# driverboard.net
KiCad netlist of a schematic drawn in Altium Designer
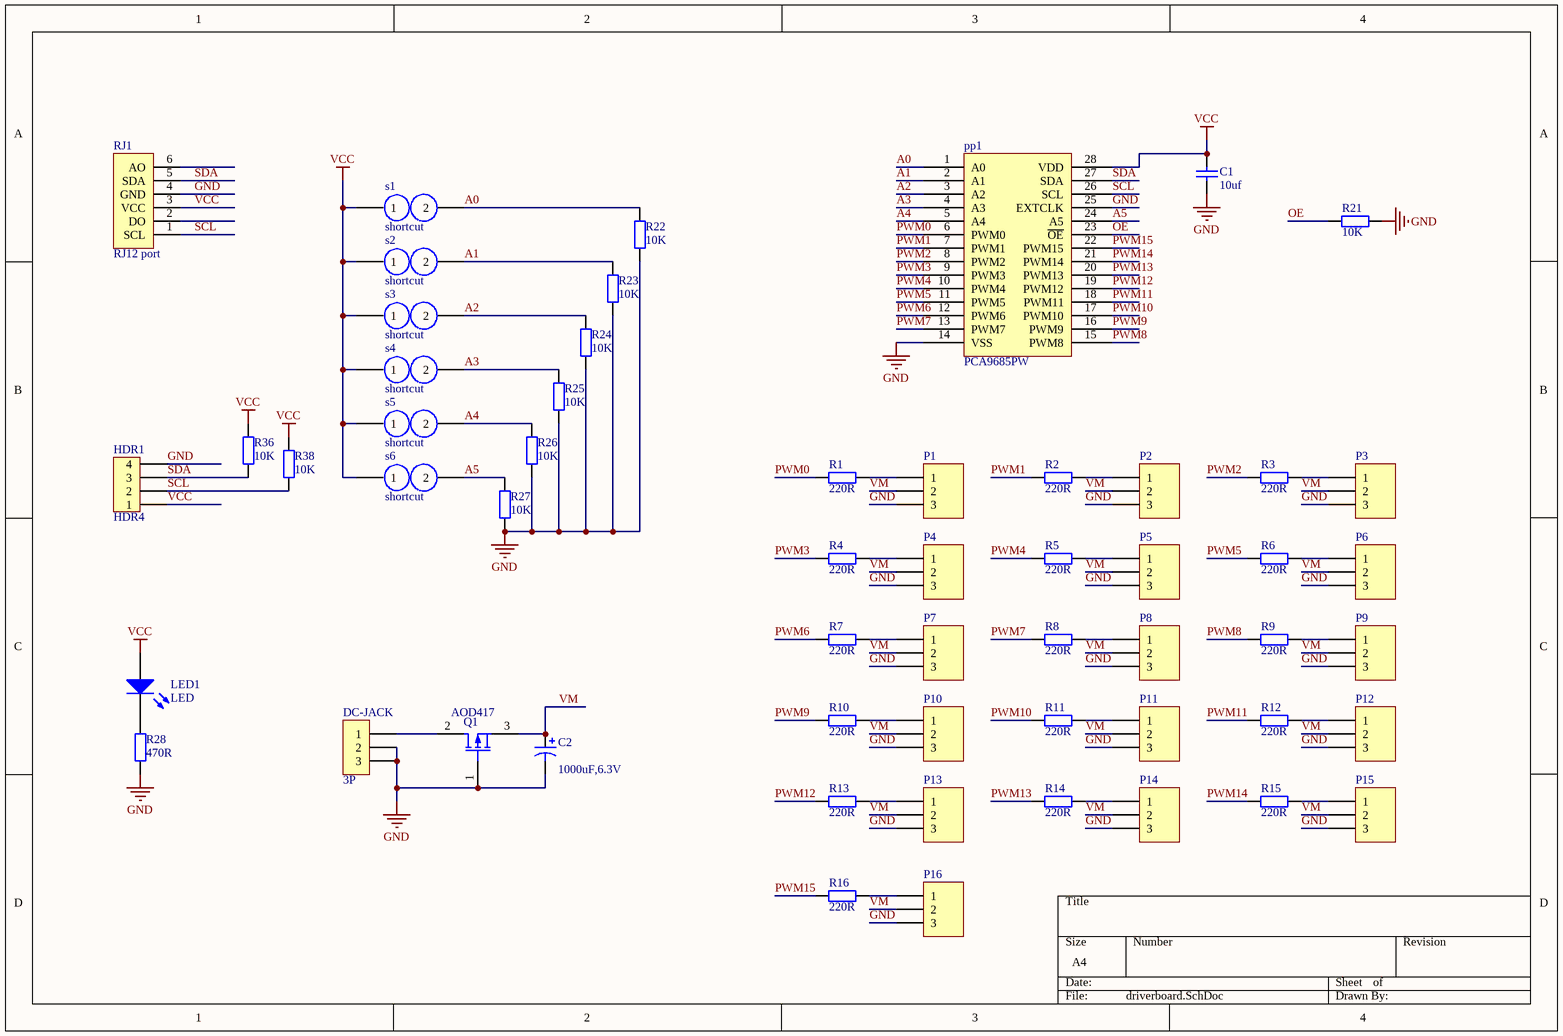
[diagram p0: driverboard.SchDoc]

(export (version "E")
  (design (tool "Eeschema 10.0.6"))
  (components
    (comp (ref "C1")
      (value "10uf")
      (footprint "C0805")
      (description "Capacitor")
      (fields (field (name "PUBLISHER") "Altium Limited"))
      (libsource (lib "apollo") (part "Capacitor"))
    )
    (comp (ref "C2")
      (value "1000uF,6.3V")
      (footprint "TC7343-E")
      (description "Polarized Capacitor (Surface Mount)")
      (fields (field (name "Comment") "Cap Pol3") (field (name "PUBLISHER") "Altium Limited"))
      (libsource (lib "Miscellaneous Devices") (part "Cap Pol3"))
    )
    (comp (ref "DC-JACK")
      (value "3P")
      (footprint "DC-JACK-005")
      (libsource (lib "UP-ROBOT Devices") (part "3P"))
    )
    (comp (ref "HDR1")
      (value "HDR4")
      (footprint "HDR1X4")
      (description "Header  4pin")
      (libsource (lib "apollo") (part "HDR4-2.54mm"))
    )
    (comp (ref "LED1")
      (value "LED")
      (footprint "C0603")
      (description "LED  SMD")
      (libsource (lib "apollo") (part "LED-SM"))
    )
    (comp (ref "P1")
      (value "Header 3H")
      (footprint "HDR1X3")
      (description "Header, 3-Pin, Right Angle")
      (fields (field (name "PUBLISHER") "Altium Limited"))
      (libsource (lib "Miscellaneous Connectors") (part "Header 3H"))
    )
    (comp (ref "P2")
      (value "Header 3H")
      (footprint "HDR1X3")
      (description "Header, 3-Pin, Right Angle")
      (fields (field (name "PUBLISHER") "Altium Limited"))
      (libsource (lib "Miscellaneous Connectors") (part "Header 3H"))
    )
    (comp (ref "P3")
      (value "Header 3H")
      (footprint "HDR1X3")
      (description "Header, 3-Pin, Right Angle")
      (fields (field (name "PUBLISHER") "Altium Limited"))
      (libsource (lib "Miscellaneous Connectors") (part "Header 3H"))
    )
    (comp (ref "P4")
      (value "Header 3H")
      (footprint "HDR1X3")
      (description "Header, 3-Pin, Right Angle")
      (fields (field (name "PUBLISHER") "Altium Limited"))
      (libsource (lib "Miscellaneous Connectors") (part "Header 3H"))
    )
    (comp (ref "P5")
      (value "Header 3H")
      (footprint "HDR1X3")
      (description "Header, 3-Pin, Right Angle")
      (fields (field (name "PUBLISHER") "Altium Limited"))
      (libsource (lib "Miscellaneous Connectors") (part "Header 3H"))
    )
    (comp (ref "P6")
      (value "Header 3H")
      (footprint "HDR1X3")
      (description "Header, 3-Pin, Right Angle")
      (fields (field (name "PUBLISHER") "Altium Limited"))
      (libsource (lib "Miscellaneous Connectors") (part "Header 3H"))
    )
    (comp (ref "P7")
      (value "Header 3H")
      (footprint "HDR1X3")
      (description "Header, 3-Pin, Right Angle")
      (fields (field (name "PUBLISHER") "Altium Limited"))
      (libsource (lib "Miscellaneous Connectors") (part "Header 3H"))
    )
    (comp (ref "P8")
      (value "Header 3H")
      (footprint "HDR1X3")
      (description "Header, 3-Pin, Right Angle")
      (fields (field (name "PUBLISHER") "Altium Limited"))
      (libsource (lib "Miscellaneous Connectors") (part "Header 3H"))
    )
    (comp (ref "P9")
      (value "Header 3H")
      (footprint "HDR1X3")
      (description "Header, 3-Pin, Right Angle")
      (fields (field (name "PUBLISHER") "Altium Limited"))
      (libsource (lib "Miscellaneous Connectors") (part "Header 3H"))
    )
    (comp (ref "P10")
      (value "Header 3H")
      (footprint "HDR1X3")
      (description "Header, 3-Pin, Right Angle")
      (fields (field (name "PUBLISHER") "Altium Limited"))
      (libsource (lib "Miscellaneous Connectors") (part "Header 3H"))
    )
    (comp (ref "P11")
      (value "Header 3H")
      (footprint "HDR1X3")
      (description "Header, 3-Pin, Right Angle")
      (fields (field (name "PUBLISHER") "Altium Limited"))
      (libsource (lib "Miscellaneous Connectors") (part "Header 3H"))
    )
    (comp (ref "P12")
      (value "Header 3H")
      (footprint "HDR1X3")
      (description "Header, 3-Pin, Right Angle")
      (fields (field (name "PUBLISHER") "Altium Limited"))
      (libsource (lib "Miscellaneous Connectors") (part "Header 3H"))
    )
    (comp (ref "P13")
      (value "Header 3H")
      (footprint "HDR1X3")
      (description "Header, 3-Pin, Right Angle")
      (fields (field (name "PUBLISHER") "Altium Limited"))
      (libsource (lib "Miscellaneous Connectors") (part "Header 3H"))
    )
    (comp (ref "P14")
      (value "Header 3H")
      (footprint "HDR1X3")
      (description "Header, 3-Pin, Right Angle")
      (fields (field (name "PUBLISHER") "Altium Limited"))
      (libsource (lib "Miscellaneous Connectors") (part "Header 3H"))
    )
    (comp (ref "P15")
      (value "Header 3H")
      (footprint "HDR1X3")
      (description "Header, 3-Pin, Right Angle")
      (fields (field (name "PUBLISHER") "Altium Limited"))
      (libsource (lib "Miscellaneous Connectors") (part "Header 3H"))
    )
    (comp (ref "P16")
      (value "Header 3H")
      (footprint "HDR1X3")
      (description "Header, 3-Pin, Right Angle")
      (fields (field (name "PUBLISHER") "Altium Limited"))
      (libsource (lib "Miscellaneous Connectors") (part "Header 3H"))
    )
    (comp (ref "pp1")
      (value "PCA9685PW")
      (footprint "TSSOP-28")
      (libsource (lib "apollo") (part "PCA9685PW"))
    )
    (comp (ref "Q1")
      (value "AOD417")
      (footprint "TO-252")
      (description "P-Channel MOSFET")
      (fields (field (name "PUBLISHER") "Altium Limited"))
      (libsource (lib "apollo") (part "MOSFET-P"))
    )
    (comp (ref "R1")
      (value "220R")
      (footprint "R0603")
      (description "Resistor")
      (fields (field (name "PUBLISHER") "Altium Limited"))
      (libsource (lib "apollo") (part "Resistor"))
    )
    (comp (ref "R2")
      (value "220R")
      (footprint "R0603")
      (description "Resistor")
      (fields (field (name "PUBLISHER") "Altium Limited"))
      (libsource (lib "apollo") (part "Resistor"))
    )
    (comp (ref "R3")
      (value "220R")
      (footprint "R0603")
      (description "Resistor")
      (fields (field (name "PUBLISHER") "Altium Limited"))
      (libsource (lib "apollo") (part "Resistor"))
    )
    (comp (ref "R4")
      (value "220R")
      (footprint "R0603")
      (description "Resistor")
      (fields (field (name "PUBLISHER") "Altium Limited"))
      (libsource (lib "apollo") (part "Resistor"))
    )
    (comp (ref "R5")
      (value "220R")
      (footprint "R0603")
      (description "Resistor")
      (fields (field (name "PUBLISHER") "Altium Limited"))
      (libsource (lib "apollo") (part "Resistor"))
    )
    (comp (ref "R6")
      (value "220R")
      (footprint "R0603")
      (description "Resistor")
      (fields (field (name "PUBLISHER") "Altium Limited"))
      (libsource (lib "apollo") (part "Resistor"))
    )
    (comp (ref "R7")
      (value "220R")
      (footprint "R0603")
      (description "Resistor")
      (fields (field (name "PUBLISHER") "Altium Limited"))
      (libsource (lib "apollo") (part "Resistor"))
    )
    (comp (ref "R8")
      (value "220R")
      (footprint "R0603")
      (description "Resistor")
      (fields (field (name "PUBLISHER") "Altium Limited"))
      (libsource (lib "apollo") (part "Resistor"))
    )
    (comp (ref "R9")
      (value "220R")
      (footprint "R0603")
      (description "Resistor")
      (fields (field (name "PUBLISHER") "Altium Limited"))
      (libsource (lib "apollo") (part "Resistor"))
    )
    (comp (ref "R10")
      (value "220R")
      (footprint "R0603")
      (description "Resistor")
      (fields (field (name "PUBLISHER") "Altium Limited"))
      (libsource (lib "apollo") (part "Resistor"))
    )
    (comp (ref "R11")
      (value "220R")
      (footprint "R0603")
      (description "Resistor")
      (fields (field (name "PUBLISHER") "Altium Limited"))
      (libsource (lib "apollo") (part "Resistor"))
    )
    (comp (ref "R12")
      (value "220R")
      (footprint "R0603")
      (description "Resistor")
      (fields (field (name "PUBLISHER") "Altium Limited"))
      (libsource (lib "apollo") (part "Resistor"))
    )
    (comp (ref "R13")
      (value "220R")
      (footprint "R0603")
      (description "Resistor")
      (fields (field (name "PUBLISHER") "Altium Limited"))
      (libsource (lib "apollo") (part "Resistor"))
    )
    (comp (ref "R14")
      (value "220R")
      (footprint "R0603")
      (description "Resistor")
      (fields (field (name "PUBLISHER") "Altium Limited"))
      (libsource (lib "apollo") (part "Resistor"))
    )
    (comp (ref "R15")
      (value "220R")
      (footprint "R0603")
      (description "Resistor")
      (fields (field (name "PUBLISHER") "Altium Limited"))
      (libsource (lib "apollo") (part "Resistor"))
    )
    (comp (ref "R16")
      (value "220R")
      (footprint "R0603")
      (description "Resistor")
      (fields (field (name "PUBLISHER") "Altium Limited"))
      (libsource (lib "apollo") (part "Resistor"))
    )
    (comp (ref "R21")
      (value "10K")
      (footprint "R0603")
      (description "Resistor")
      (fields (field (name "PUBLISHER") "Altium Limited"))
      (libsource (lib "apollo") (part "Resistor"))
    )
    (comp (ref "R22")
      (value "10K")
      (footprint "R0603")
      (description "Resistor")
      (fields (field (name "PUBLISHER") "Altium Limited"))
      (libsource (lib "") (part "Resistor_1"))
    )
    (comp (ref "R23")
      (value "10K")
      (footprint "R0603")
      (description "Resistor")
      (fields (field (name "PUBLISHER") "Altium Limited"))
      (libsource (lib "") (part "Resistor_1"))
    )
    (comp (ref "R24")
      (value "10K")
      (footprint "R0603")
      (description "Resistor")
      (fields (field (name "PUBLISHER") "Altium Limited"))
      (libsource (lib "") (part "Resistor_1"))
    )
    (comp (ref "R25")
      (value "10K")
      (footprint "R0603")
      (description "Resistor")
      (fields (field (name "PUBLISHER") "Altium Limited"))
      (libsource (lib "") (part "Resistor_1"))
    )
    (comp (ref "R26")
      (value "10K")
      (footprint "R0603")
      (description "Resistor")
      (fields (field (name "PUBLISHER") "Altium Limited"))
      (libsource (lib "") (part "Resistor_1"))
    )
    (comp (ref "R27")
      (value "10K")
      (footprint "R0603")
      (description "Resistor")
      (fields (field (name "PUBLISHER") "Altium Limited"))
      (libsource (lib "") (part "Resistor_1"))
    )
    (comp (ref "R28")
      (value "470R")
      (footprint "R0603")
      (description "Resistor")
      (fields (field (name "PUBLISHER") "Altium Limited"))
      (libsource (lib "") (part "Resistor_1"))
    )
    (comp (ref "R36")
      (value "10K")
      (footprint "R0603")
      (description "Resistor")
      (fields (field (name "PUBLISHER") "Altium Limited"))
      (libsource (lib "") (part "Resistor_1"))
    )
    (comp (ref "R38")
      (value "10K")
      (footprint "R0603")
      (description "Resistor")
      (fields (field (name "PUBLISHER") "Altium Limited"))
      (libsource (lib "") (part "Resistor_1"))
    )
    (comp (ref "RJ1")
      (value "RJ12 port")
      (footprint "RJ12-S-12X15X14.5")
      (libsource (lib "apollo") (part "RJ12"))
    )
    (comp (ref "s1") (value "shortcut") (footprint "C0603") (libsource (lib "apollo") (part "shortcut")))
    (comp (ref "s2") (value "shortcut") (footprint "C0603") (libsource (lib "apollo") (part "shortcut")))
    (comp (ref "s3") (value "shortcut") (footprint "C0603") (libsource (lib "apollo") (part "shortcut")))
    (comp (ref "s4") (value "shortcut") (footprint "C0603") (libsource (lib "apollo") (part "shortcut")))
    (comp (ref "s5") (value "shortcut") (footprint "C0603") (libsource (lib "apollo") (part "shortcut")))
    (comp (ref "s6") (value "shortcut") (footprint "C0603") (libsource (lib "apollo") (part "shortcut")))
  )
  (nets
    (net (code "1") (name "/A0") (class "Default")
      (node (ref "R22") (pin "2") (pinfunction "2_2") (pintype "passive"))
      (node (ref "pp1") (pin "1") (pinfunction "A0_1") (pintype "passive"))
      (node (ref "s1") (pin "2") (pinfunction "2_2") (pintype "passive"))
    )
    (net (code "2") (name "/A1") (class "Default")
      (node (ref "R23") (pin "2") (pinfunction "2_2") (pintype "passive"))
      (node (ref "pp1") (pin "2") (pinfunction "A1_2") (pintype "passive"))
      (node (ref "s2") (pin "2") (pinfunction "2_2") (pintype "passive"))
    )
    (net (code "3") (name "/A2") (class "Default")
      (node (ref "R24") (pin "2") (pinfunction "2_2") (pintype "passive"))
      (node (ref "pp1") (pin "3") (pinfunction "A2_3") (pintype "passive"))
      (node (ref "s3") (pin "2") (pinfunction "2_2") (pintype "passive"))
    )
    (net (code "4") (name "/A3") (class "Default")
      (node (ref "R25") (pin "2") (pinfunction "2_2") (pintype "passive"))
      (node (ref "pp1") (pin "4") (pinfunction "A3_4") (pintype "passive"))
      (node (ref "s4") (pin "2") (pinfunction "2_2") (pintype "passive"))
    )
    (net (code "5") (name "/A4") (class "Default")
      (node (ref "R26") (pin "2") (pinfunction "2_2") (pintype "passive"))
      (node (ref "pp1") (pin "5") (pinfunction "A4_5") (pintype "passive"))
      (node (ref "s5") (pin "2") (pinfunction "2_2") (pintype "passive"))
    )
    (net (code "6") (name "/A5") (class "Default")
      (node (ref "R27") (pin "2") (pinfunction "2_2") (pintype "passive"))
      (node (ref "pp1") (pin "24") (pinfunction "A5_24") (pintype "passive"))
      (node (ref "s6") (pin "2") (pinfunction "2_2") (pintype "passive"))
    )
    (net (code "7") (name "/OE") (class "Default")
      (node (ref "R21") (pin "2") (pinfunction "2_2") (pintype "passive"))
      (node (ref "pp1") (pin "23") (pinfunction "~{OE}_23") (pintype "passive"))
    )
    (net (code "8") (name "/PWM0") (class "Default")
      (node (ref "R1") (pin "2") (pinfunction "2_2") (pintype "passive"))
      (node (ref "pp1") (pin "6") (pinfunction "PWM0_6") (pintype "passive"))
    )
    (net (code "9") (name "/PWM1") (class "Default")
      (node (ref "R2") (pin "2") (pinfunction "2_2") (pintype "passive"))
      (node (ref "pp1") (pin "7") (pinfunction "PWM1_7") (pintype "passive"))
    )
    (net (code "10") (name "/PWM2") (class "Default")
      (node (ref "R3") (pin "2") (pinfunction "2_2") (pintype "passive"))
      (node (ref "pp1") (pin "8") (pinfunction "PWM2_8") (pintype "passive"))
    )
    (net (code "11") (name "/PWM3") (class "Default")
      (node (ref "R4") (pin "2") (pinfunction "2_2") (pintype "passive"))
      (node (ref "pp1") (pin "9") (pinfunction "PWM3_9") (pintype "passive"))
    )
    (net (code "12") (name "/PWM4") (class "Default")
      (node (ref "R5") (pin "2") (pinfunction "2_2") (pintype "passive"))
      (node (ref "pp1") (pin "10") (pinfunction "PWM4_10") (pintype "passive"))
    )
    (net (code "13") (name "/PWM5") (class "Default")
      (node (ref "R6") (pin "2") (pinfunction "2_2") (pintype "passive"))
      (node (ref "pp1") (pin "11") (pinfunction "PWM5_11") (pintype "passive"))
    )
    (net (code "14") (name "/PWM6") (class "Default")
      (node (ref "R7") (pin "2") (pinfunction "2_2") (pintype "passive"))
      (node (ref "pp1") (pin "12") (pinfunction "PWM6_12") (pintype "passive"))
    )
    (net (code "15") (name "/PWM7") (class "Default")
      (node (ref "R8") (pin "2") (pinfunction "2_2") (pintype "passive"))
      (node (ref "pp1") (pin "13") (pinfunction "PWM7_13") (pintype "passive"))
    )
    (net (code "16") (name "/PWM8") (class "Default")
      (node (ref "R9") (pin "2") (pinfunction "2_2") (pintype "passive"))
      (node (ref "pp1") (pin "15") (pinfunction "PWM8_15") (pintype "passive"))
    )
    (net (code "17") (name "/PWM9") (class "Default")
      (node (ref "R10") (pin "2") (pinfunction "2_2") (pintype "passive"))
      (node (ref "pp1") (pin "16") (pinfunction "PWM9_16") (pintype "passive"))
    )
    (net (code "18") (name "/PWM10") (class "Default")
      (node (ref "R11") (pin "2") (pinfunction "2_2") (pintype "passive"))
      (node (ref "pp1") (pin "17") (pinfunction "PWM10_17") (pintype "passive"))
    )
    (net (code "19") (name "/PWM11") (class "Default")
      (node (ref "R12") (pin "2") (pinfunction "2_2") (pintype "passive"))
      (node (ref "pp1") (pin "18") (pinfunction "PWM11_18") (pintype "passive"))
    )
    (net (code "20") (name "/PWM12") (class "Default")
      (node (ref "R13") (pin "2") (pinfunction "2_2") (pintype "passive"))
      (node (ref "pp1") (pin "19") (pinfunction "PWM12_19") (pintype "passive"))
    )
    (net (code "21") (name "/PWM13") (class "Default")
      (node (ref "R14") (pin "2") (pinfunction "2_2") (pintype "passive"))
      (node (ref "pp1") (pin "20") (pinfunction "PWM13_20") (pintype "passive"))
    )
    (net (code "22") (name "/PWM14") (class "Default")
      (node (ref "R15") (pin "2") (pinfunction "2_2") (pintype "passive"))
      (node (ref "pp1") (pin "21") (pinfunction "PWM14_21") (pintype "passive"))
    )
    (net (code "23") (name "/PWM15") (class "Default")
      (node (ref "R16") (pin "2") (pinfunction "2_2") (pintype "passive"))
      (node (ref "pp1") (pin "22") (pinfunction "PWM15_22") (pintype "passive"))
    )
    (net (code "24") (name "/SCL") (class "Default")
      (node (ref "HDR1") (pin "2") (pinfunction "2_2") (pintype "passive"))
      (node (ref "R38") (pin "1") (pinfunction "1_1") (pintype "passive"))
      (node (ref "RJ1") (pin "1") (pinfunction "SCL_1") (pintype "passive"))
      (node (ref "pp1") (pin "26") (pinfunction "SCL_26") (pintype "passive"))
    )
    (net (code "25") (name "/SDA") (class "Default")
      (node (ref "HDR1") (pin "3") (pinfunction "3_3") (pintype "passive"))
      (node (ref "R36") (pin "1") (pinfunction "1_1") (pintype "passive"))
      (node (ref "RJ1") (pin "5") (pinfunction "SDA_5") (pintype "passive"))
      (node (ref "pp1") (pin "27") (pinfunction "SDA_27") (pintype "passive"))
    )
    (net (code "26") (name "/VM") (class "Default")
      (node (ref "C2") (pin "1") (pinfunction "1_1") (pintype "passive"))
      (node (ref "P1") (pin "2") (pinfunction "2_2") (pintype "passive"))
      (node (ref "P10") (pin "2") (pinfunction "2_2") (pintype "passive"))
      (node (ref "P11") (pin "2") (pinfunction "2_2") (pintype "passive"))
      (node (ref "P12") (pin "2") (pinfunction "2_2") (pintype "passive"))
      (node (ref "P13") (pin "2") (pinfunction "2_2") (pintype "passive"))
      (node (ref "P14") (pin "2") (pinfunction "2_2") (pintype "passive"))
      (node (ref "P15") (pin "2") (pinfunction "2_2") (pintype "passive"))
      (node (ref "P16") (pin "2") (pinfunction "2_2") (pintype "passive"))
      (node (ref "P2") (pin "2") (pinfunction "2_2") (pintype "passive"))
      (node (ref "P3") (pin "2") (pinfunction "2_2") (pintype "passive"))
      (node (ref "P4") (pin "2") (pinfunction "2_2") (pintype "passive"))
      (node (ref "P5") (pin "2") (pinfunction "2_2") (pintype "passive"))
      (node (ref "P6") (pin "2") (pinfunction "2_2") (pintype "passive"))
      (node (ref "P7") (pin "2") (pinfunction "2_2") (pintype "passive"))
      (node (ref "P8") (pin "2") (pinfunction "2_2") (pintype "passive"))
      (node (ref "P9") (pin "2") (pinfunction "2_2") (pintype "passive"))
      (node (ref "Q1") (pin "3") (pinfunction "S_3") (pintype "passive"))
    )
    (net (code "27") (name "GND") (class "Default")
      (node (ref "C1") (pin "1") (pinfunction "1_1") (pintype "passive"))
      (node (ref "C2") (pin "2") (pinfunction "2_2") (pintype "passive"))
      (node (ref "DC-JACK") (pin "2") (pinfunction "2_2") (pintype "passive"))
      (node (ref "DC-JACK") (pin "3") (pinfunction "3_3") (pintype "passive"))
      (node (ref "HDR1") (pin "4") (pinfunction "4_4") (pintype "passive"))
      (node (ref "P1") (pin "3") (pinfunction "3_3") (pintype "passive"))
      (node (ref "P10") (pin "3") (pinfunction "3_3") (pintype "passive"))
      (node (ref "P11") (pin "3") (pinfunction "3_3") (pintype "passive"))
      (node (ref "P12") (pin "3") (pinfunction "3_3") (pintype "passive"))
      (node (ref "P13") (pin "3") (pinfunction "3_3") (pintype "passive"))
      (node (ref "P14") (pin "3") (pinfunction "3_3") (pintype "passive"))
      (node (ref "P15") (pin "3") (pinfunction "3_3") (pintype "passive"))
      (node (ref "P16") (pin "3") (pinfunction "3_3") (pintype "passive"))
      (node (ref "P2") (pin "3") (pinfunction "3_3") (pintype "passive"))
      (node (ref "P3") (pin "3") (pinfunction "3_3") (pintype "passive"))
      (node (ref "P4") (pin "3") (pinfunction "3_3") (pintype "passive"))
      (node (ref "P5") (pin "3") (pinfunction "3_3") (pintype "passive"))
      (node (ref "P6") (pin "3") (pinfunction "3_3") (pintype "passive"))
      (node (ref "P7") (pin "3") (pinfunction "3_3") (pintype "passive"))
      (node (ref "P8") (pin "3") (pinfunction "3_3") (pintype "passive"))
      (node (ref "P9") (pin "3") (pinfunction "3_3") (pintype "passive"))
      (node (ref "Q1") (pin "1") (pinfunction "G_1") (pintype "passive"))
      (node (ref "R21") (pin "1") (pinfunction "1_1") (pintype "passive"))
      (node (ref "R22") (pin "1") (pinfunction "1_1") (pintype "passive"))
      (node (ref "R23") (pin "1") (pinfunction "1_1") (pintype "passive"))
      (node (ref "R24") (pin "1") (pinfunction "1_1") (pintype "passive"))
      (node (ref "R25") (pin "1") (pinfunction "1_1") (pintype "passive"))
      (node (ref "R26") (pin "1") (pinfunction "1_1") (pintype "passive"))
      (node (ref "R27") (pin "1") (pinfunction "1_1") (pintype "passive"))
      (node (ref "R28") (pin "1") (pinfunction "1_1") (pintype "passive"))
      (node (ref "RJ1") (pin "4") (pinfunction "GND_4") (pintype "passive"))
      (node (ref "pp1") (pin "14") (pinfunction "VSS_14") (pintype "passive"))
      (node (ref "pp1") (pin "25") (pinfunction "EXTCLK_25") (pintype "passive"))
    )
    (net (code "28") (name "Net-(LED1-K)") (class "Default")
      (node (ref "LED1") (pin "2") (pinfunction "K_2") (pintype "passive"))
      (node (ref "R28") (pin "2") (pinfunction "2_2") (pintype "passive"))
    )
    (net (code "29") (name "Net-(P1-Pad1)") (class "Default")
      (node (ref "P1") (pin "1") (pinfunction "1_1") (pintype "passive"))
      (node (ref "R1") (pin "1") (pinfunction "1_1") (pintype "passive"))
    )
    (net (code "30") (name "Net-(P2-Pad1)") (class "Default")
      (node (ref "P2") (pin "1") (pinfunction "1_1") (pintype "passive"))
      (node (ref "R2") (pin "1") (pinfunction "1_1") (pintype "passive"))
    )
    (net (code "31") (name "Net-(P3-Pad1)") (class "Default")
      (node (ref "P3") (pin "1") (pinfunction "1_1") (pintype "passive"))
      (node (ref "R3") (pin "1") (pinfunction "1_1") (pintype "passive"))
    )
    (net (code "32") (name "Net-(P4-Pad1)") (class "Default")
      (node (ref "P4") (pin "1") (pinfunction "1_1") (pintype "passive"))
      (node (ref "R4") (pin "1") (pinfunction "1_1") (pintype "passive"))
    )
    (net (code "33") (name "Net-(P5-Pad1)") (class "Default")
      (node (ref "P5") (pin "1") (pinfunction "1_1") (pintype "passive"))
      (node (ref "R5") (pin "1") (pinfunction "1_1") (pintype "passive"))
    )
    (net (code "34") (name "Net-(P6-Pad1)") (class "Default")
      (node (ref "P6") (pin "1") (pinfunction "1_1") (pintype "passive"))
      (node (ref "R6") (pin "1") (pinfunction "1_1") (pintype "passive"))
    )
    (net (code "35") (name "Net-(P7-Pad1)") (class "Default")
      (node (ref "P7") (pin "1") (pinfunction "1_1") (pintype "passive"))
      (node (ref "R7") (pin "1") (pinfunction "1_1") (pintype "passive"))
    )
    (net (code "36") (name "Net-(P8-Pad1)") (class "Default")
      (node (ref "P8") (pin "1") (pinfunction "1_1") (pintype "passive"))
      (node (ref "R8") (pin "1") (pinfunction "1_1") (pintype "passive"))
    )
    (net (code "37") (name "Net-(P9-Pad1)") (class "Default")
      (node (ref "P9") (pin "1") (pinfunction "1_1") (pintype "passive"))
      (node (ref "R9") (pin "1") (pinfunction "1_1") (pintype "passive"))
    )
    (net (code "38") (name "Net-(P10-Pad1)") (class "Default")
      (node (ref "P10") (pin "1") (pinfunction "1_1") (pintype "passive"))
      (node (ref "R10") (pin "1") (pinfunction "1_1") (pintype "passive"))
    )
    (net (code "39") (name "Net-(P11-Pad1)") (class "Default")
      (node (ref "P11") (pin "1") (pinfunction "1_1") (pintype "passive"))
      (node (ref "R11") (pin "1") (pinfunction "1_1") (pintype "passive"))
    )
    (net (code "40") (name "Net-(P12-Pad1)") (class "Default")
      (node (ref "P12") (pin "1") (pinfunction "1_1") (pintype "passive"))
      (node (ref "R12") (pin "1") (pinfunction "1_1") (pintype "passive"))
    )
    (net (code "41") (name "Net-(P13-Pad1)") (class "Default")
      (node (ref "P13") (pin "1") (pinfunction "1_1") (pintype "passive"))
      (node (ref "R13") (pin "1") (pinfunction "1_1") (pintype "passive"))
    )
    (net (code "42") (name "Net-(P14-Pad1)") (class "Default")
      (node (ref "P14") (pin "1") (pinfunction "1_1") (pintype "passive"))
      (node (ref "R14") (pin "1") (pinfunction "1_1") (pintype "passive"))
    )
    (net (code "43") (name "Net-(P15-Pad1)") (class "Default")
      (node (ref "P15") (pin "1") (pinfunction "1_1") (pintype "passive"))
      (node (ref "R15") (pin "1") (pinfunction "1_1") (pintype "passive"))
    )
    (net (code "44") (name "Net-(P16-Pad1)") (class "Default")
      (node (ref "P16") (pin "1") (pinfunction "1_1") (pintype "passive"))
      (node (ref "R16") (pin "1") (pinfunction "1_1") (pintype "passive"))
    )
    (net (code "45") (name "Net-(Q1-D)") (class "Default")
      (node (ref "DC-JACK") (pin "1") (pinfunction "1_1") (pintype "passive"))
      (node (ref "Q1") (pin "2") (pinfunction "D_2") (pintype "passive"))
    )
    (net (code "46") (name "VCC") (class "Default")
      (node (ref "C1") (pin "2") (pinfunction "2_2") (pintype "passive"))
      (node (ref "HDR1") (pin "1") (pinfunction "1_1") (pintype "passive"))
      (node (ref "LED1") (pin "1") (pinfunction "A_1") (pintype "passive"))
      (node (ref "R36") (pin "2") (pinfunction "2_2") (pintype "passive"))
      (node (ref "R38") (pin "2") (pinfunction "2_2") (pintype "passive"))
      (node (ref "RJ1") (pin "3") (pinfunction "VCC_3") (pintype "passive"))
      (node (ref "pp1") (pin "28") (pinfunction "VDD_28") (pintype "passive"))
      (node (ref "s1") (pin "1") (pinfunction "1_1") (pintype "passive"))
      (node (ref "s2") (pin "1") (pinfunction "1_1") (pintype "passive"))
      (node (ref "s3") (pin "1") (pinfunction "1_1") (pintype "passive"))
      (node (ref "s4") (pin "1") (pinfunction "1_1") (pintype "passive"))
      (node (ref "s5") (pin "1") (pinfunction "1_1") (pintype "passive"))
      (node (ref "s6") (pin "1") (pinfunction "1_1") (pintype "passive"))
    )
    (net (code "47") (name "unconnected-(RJ1-AO-Pad6)") (class "Default")
      (node (ref "RJ1") (pin "6") (pinfunction "AO_6") (pintype "passive"))
    )
    (net (code "48") (name "unconnected-(RJ1-DO-Pad2)") (class "Default")
      (node (ref "RJ1") (pin "2") (pinfunction "DO_2") (pintype "passive"))
    )
  )
)
